# DSO_Power.net
KiCad netlist of a schematic drawn in Altium Designer
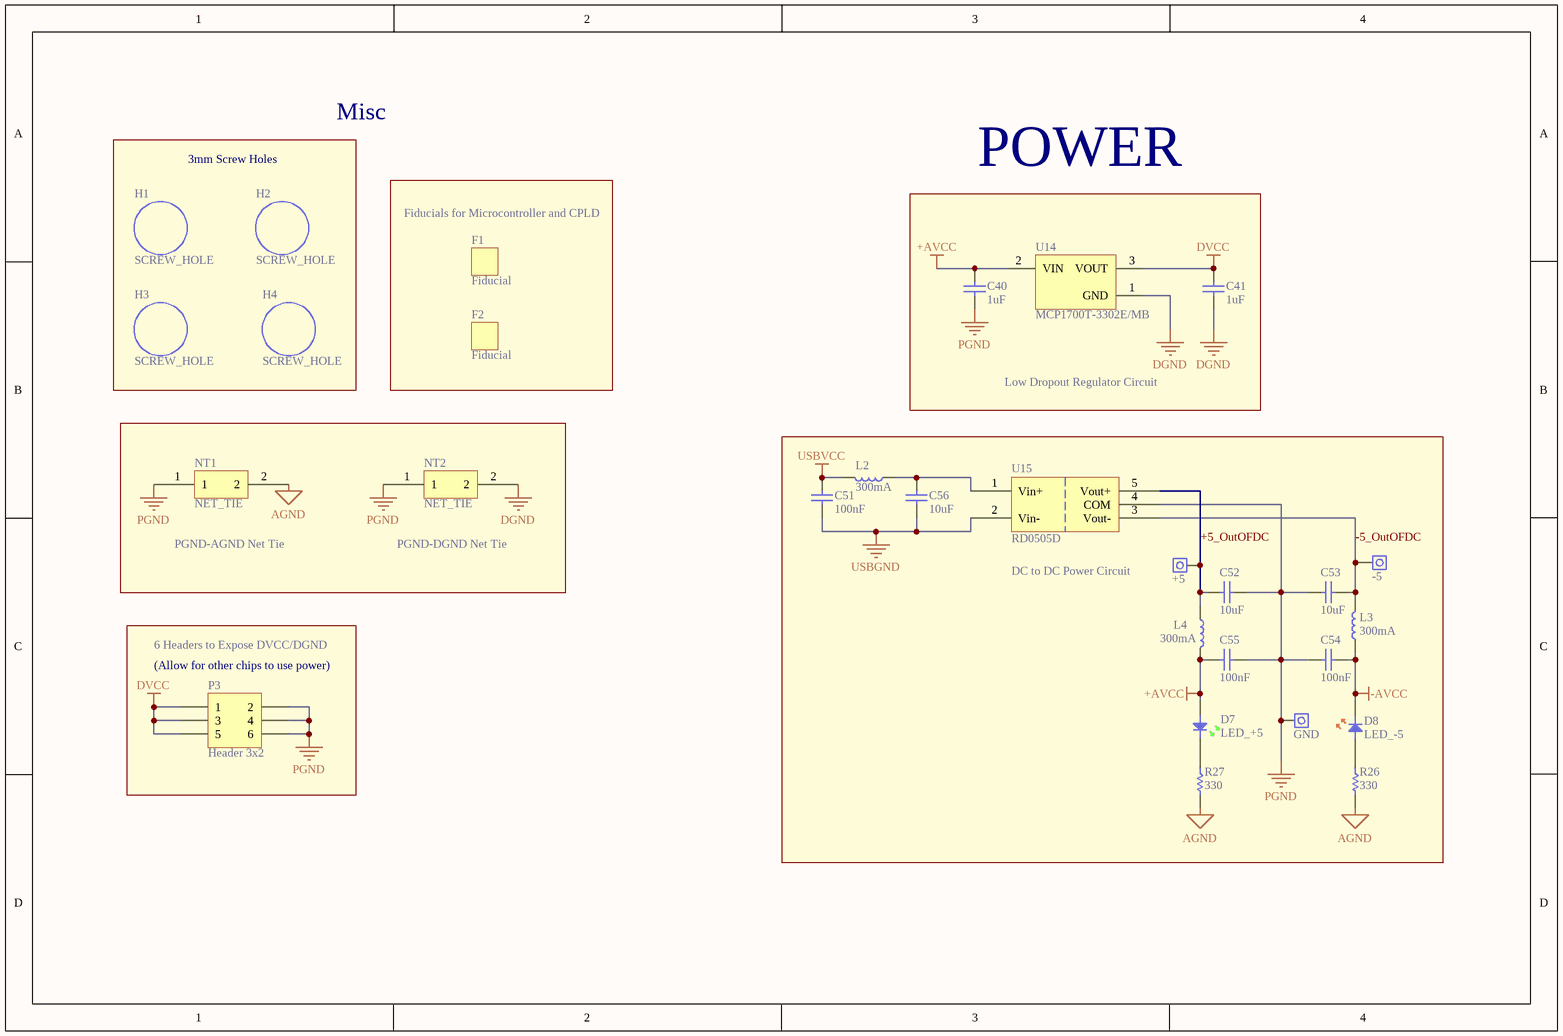
[diagram p0: DSO_Power.SchDoc]

(export (version "E")
  (design (tool "Eeschema 10.0.6"))
  (components
    (comp (ref "C40")
      (value "1uF")
      (footprint "0805C")
      (description "Capacitor")
      (fields (field (name "REVIEWED BY") "RM - 2018/08/05"))
      (libsource (lib "DSO") (part "C"))
    )
    (comp (ref "C41")
      (value "1uF")
      (footprint "0805C")
      (description "Capacitor")
      (fields (field (name "REVIEWED BY") "RM - 2018/08/05"))
      (libsource (lib "DSO") (part "C"))
    )
    (comp (ref "C51")
      (value "100nF")
      (footprint "0805C")
      (description "Capacitor")
      (fields (field (name "REVIEWED BY") "RM - 2018/08/05"))
      (libsource (lib "DSO") (part "C"))
    )
    (comp (ref "C52")
      (value "10uF")
      (footprint "0805C")
      (description "Capacitor")
      (fields (field (name "REVIEWED BY") "RM - 2018/08/05"))
      (libsource (lib "DSO") (part "C"))
    )
    (comp (ref "C53")
      (value "10uF")
      (footprint "0805C")
      (description "Capacitor")
      (fields (field (name "REVIEWED BY") "RM - 2018/08/05"))
      (libsource (lib "DSO") (part "C"))
    )
    (comp (ref "C54")
      (value "100nF")
      (footprint "0805C")
      (description "Capacitor")
      (fields (field (name "REVIEWED BY") "RM - 2018/08/05"))
      (libsource (lib "DSO") (part "C"))
    )
    (comp (ref "C55")
      (value "100nF")
      (footprint "0805C")
      (description "Capacitor")
      (fields (field (name "REVIEWED BY") "RM - 2018/08/05"))
      (libsource (lib "DSO") (part "C"))
    )
    (comp (ref "C56")
      (value "10uF")
      (footprint "0805C")
      (description "Capacitor")
      (fields (field (name "REVIEWED BY") "RM - 2018/08/05"))
      (libsource (lib "DSO") (part "C"))
    )
    (comp (ref "D7")
      (value "LED_+5")
      (footprint "0805D-GREEN")
      (description "Light Emitting Diode")
      (fields (field (name "REVIEWED BY") "RM - 2018/08/05"))
      (libsource (lib "DSO") (part "LED GREEN"))
    )
    (comp (ref "D8")
      (value "LED_-5")
      (footprint "0805D-RED")
      (description "Light Emitting Diode")
      (fields (field (name "REVIEWED BY") "RM - 2018/08/05"))
      (libsource (lib "DSO") (part "LED RED"))
    )
    (comp (ref "F1") (value "Fiducial") (footprint "Fiducial") (libsource (lib "DSO") (part "Fiducial")))
    (comp (ref "F2") (value "Fiducial") (footprint "Fiducial") (libsource (lib "DSO") (part "Fiducial")))
    (comp (ref "H1")
      (value "SCREW_HOLE")
      (footprint "SCREW_HOLE")
      (libsource (lib "DSO") (part "SCREW_HOLE"))
    )
    (comp (ref "H2")
      (value "SCREW_HOLE")
      (footprint "SCREW_HOLE")
      (libsource (lib "DSO") (part "SCREW_HOLE"))
    )
    (comp (ref "H3")
      (value "SCREW_HOLE")
      (footprint "SCREW_HOLE")
      (libsource (lib "DSO") (part "SCREW_HOLE"))
    )
    (comp (ref "H4")
      (value "SCREW_HOLE")
      (footprint "SCREW_HOLE")
      (libsource (lib "DSO") (part "SCREW_HOLE"))
    )
    (comp (ref "L2")
      (value "300mA")
      (footprint "0805")
      (description "Inductor")
      (fields (field (name "REVIEWED BY") "RM - 2018/08/05"))
      (libsource (lib "DSO") (part "I"))
    )
    (comp (ref "L3")
      (value "300mA")
      (footprint "0805")
      (description "Inductor")
      (fields (field (name "REVIEWED BY") "RM - 2018/08/05"))
      (libsource (lib "DSO") (part "I"))
    )
    (comp (ref "L4")
      (value "300mA")
      (footprint "0805")
      (description "Inductor")
      (fields (field (name "REVIEWED BY") "RM - 2018/08/05"))
      (libsource (lib "DSO") (part "I"))
    )
    (comp (ref "NT1")
      (value "NET_TIE")
      (footprint "NET_TIE")
      (description "Net Tie")
      (libsource (lib "DSO") (part "NET_TIE"))
    )
    (comp (ref "NT2")
      (value "NET_TIE")
      (footprint "NET_TIE")
      (description "Net Tie")
      (libsource (lib "DSO") (part "NET_TIE"))
    )
    (comp (ref "P3")
      (value "Header 3x2")
      (footprint "HDR3x2")
      (description "Header, 5-Pin")
      (fields (field (name "REVIEWED BY") "RM - 2018/08/05"))
      (libsource (lib "DSO") (part "Header 3x2"))
    )
    (comp (ref "R26")
      (value "330")
      (footprint "0805")
      (description "Resistor")
      (fields (field (name "REVIEWED BY") "RM - 2018/08/05"))
      (libsource (lib "DSO") (part "R"))
    )
    (comp (ref "R27")
      (value "330")
      (footprint "0805")
      (description "Resistor")
      (fields (field (name "REVIEWED BY") "RM - 2018/08/05"))
      (libsource (lib "DSO") (part "R"))
    )
    (comp (ref "TP9")
      (value "-5")
      (footprint "PIN 1.8mm")
      (description "Pad")
      (libsource (lib "DSO") (part "WIRE"))
    )
    (comp (ref "TP10")
      (value "GND")
      (footprint "PIN 1.8mm")
      (description "Pad")
      (libsource (lib "DSO") (part "WIRE"))
    )
    (comp (ref "TP11")
      (value "+5")
      (footprint "PIN 1.8mm")
      (description "Pad")
      (libsource (lib "DSO") (part "WIRE"))
    )
    (comp (ref "U14")
      (value "MCP1700T-3302E/MB")
      (footprint "SOT89")
      (description "Low Quiescent Current LDO, 3-Pin SOT-89, Extended Temperature, Tape and Reel")
      (fields (field (name "REVIEWED BY") "RM - 2018/08/05"))
      (libsource (lib "DSO") (part "MCP1700T"))
    )
    (comp (ref "U15")
      (value "RD0505D")
      (footprint "SIP_NMG")
      (description "(ADV) DC to DC converter 5V in +-5V out")
      (fields (field (name "REVIEWED BY") "RM - 2018/08/05"))
      (libsource (lib "DSO") (part "RD0505D"))
    )
  )
  (nets
    (net (code "1") (name "+AVCC") (class "Default")
      (node (ref "C40") (pin "1") (pinfunction "1_1") (pintype "passive"))
      (node (ref "C55") (pin "1") (pinfunction "1_1") (pintype "passive"))
      (node (ref "D7") (pin "A") (pinfunction "A_A") (pintype "passive"))
      (node (ref "L4") (pin "2") (pinfunction "2_2") (pintype "passive"))
      (node (ref "U14") (pin "2") (pinfunction "VIN_2") (pintype "power_in"))
    )
    (net (code "2") (name "-AVCC") (class "Default")
      (node (ref "C54") (pin "1") (pinfunction "1_1") (pintype "passive"))
      (node (ref "D8") (pin "K") (pinfunction "K_K") (pintype "passive"))
      (node (ref "L3") (pin "1") (pinfunction "1_1") (pintype "passive"))
    )
    (net (code "3") (name "/+5_OutOFDC") (class "Default")
      (node (ref "C52") (pin "1") (pinfunction "1_1") (pintype "passive"))
      (node (ref "L4") (pin "1") (pinfunction "1_1") (pintype "passive"))
      (node (ref "TP11") (pin "1") (pintype "passive"))
      (node (ref "U15") (pin "5") (pinfunction "Vout+_5") (pintype "passive"))
    )
    (net (code "4") (name "/-5_OutOFDC") (class "Default")
      (node (ref "C53") (pin "1") (pinfunction "1_1") (pintype "passive"))
      (node (ref "L3") (pin "2") (pinfunction "2_2") (pintype "passive"))
      (node (ref "TP9") (pin "1") (pintype "passive"))
      (node (ref "U15") (pin "3") (pinfunction "Vout-_3") (pintype "passive"))
    )
    (net (code "5") (name "AGND") (class "Default")
      (node (ref "NT1") (pin "2") (pinfunction "2_2") (pintype "passive"))
      (node (ref "R26") (pin "2") (pintype "passive"))
      (node (ref "R27") (pin "2") (pintype "passive"))
    )
    (net (code "6") (name "DGND") (class "Default")
      (node (ref "C41") (pin "2") (pinfunction "2_2") (pintype "passive"))
      (node (ref "NT2") (pin "2") (pinfunction "2_2") (pintype "passive"))
      (node (ref "U14") (pin "1") (pinfunction "GND_1") (pintype "power_in"))
    )
    (net (code "7") (name "DVCC") (class "Default")
      (node (ref "C41") (pin "1") (pinfunction "1_1") (pintype "passive"))
      (node (ref "P3") (pin "1") (pinfunction "1_1") (pintype "passive"))
      (node (ref "P3") (pin "3") (pinfunction "3_3") (pintype "passive"))
      (node (ref "P3") (pin "5") (pinfunction "5_5") (pintype "passive"))
      (node (ref "U14") (pin "3") (pinfunction "VOUT_3") (pintype "power_in"))
    )
    (net (code "8") (name "Net-(D7-PadK)") (class "Default")
      (node (ref "D7") (pin "K") (pinfunction "K_K") (pintype "passive"))
      (node (ref "R27") (pin "1") (pintype "passive"))
    )
    (net (code "9") (name "Net-(D8-PadA)") (class "Default")
      (node (ref "D8") (pin "A") (pinfunction "A_A") (pintype "passive"))
      (node (ref "R26") (pin "1") (pintype "passive"))
    )
    (net (code "10") (name "Net-(U15-Vin+)") (class "Default")
      (node (ref "C56") (pin "1") (pinfunction "1_1") (pintype "passive"))
      (node (ref "L2") (pin "1") (pinfunction "1_1") (pintype "passive"))
      (node (ref "U15") (pin "1") (pinfunction "Vin+_1") (pintype "passive"))
    )
    (net (code "11") (name "PGND") (class "Default")
      (node (ref "C40") (pin "2") (pinfunction "2_2") (pintype "passive"))
      (node (ref "C52") (pin "2") (pinfunction "2_2") (pintype "passive"))
      (node (ref "C53") (pin "2") (pinfunction "2_2") (pintype "passive"))
      (node (ref "C54") (pin "2") (pinfunction "2_2") (pintype "passive"))
      (node (ref "C55") (pin "2") (pinfunction "2_2") (pintype "passive"))
      (node (ref "NT1") (pin "1") (pinfunction "1_1") (pintype "passive"))
      (node (ref "NT2") (pin "1") (pinfunction "1_1") (pintype "passive"))
      (node (ref "P3") (pin "2") (pinfunction "2_2") (pintype "passive"))
      (node (ref "P3") (pin "4") (pinfunction "4_4") (pintype "passive"))
      (node (ref "P3") (pin "6") (pinfunction "6_6") (pintype "passive"))
      (node (ref "TP10") (pin "1") (pintype "passive"))
      (node (ref "U15") (pin "4") (pinfunction "COM_4") (pintype "passive"))
    )
    (net (code "12") (name "USBGND") (class "Default")
      (node (ref "C51") (pin "2") (pinfunction "2_2") (pintype "passive"))
      (node (ref "C56") (pin "2") (pinfunction "2_2") (pintype "passive"))
      (node (ref "U15") (pin "2") (pinfunction "Vin-_2") (pintype "passive"))
    )
    (net (code "13") (name "USBVCC") (class "Default")
      (node (ref "C51") (pin "1") (pinfunction "1_1") (pintype "passive"))
      (node (ref "L2") (pin "2") (pinfunction "2_2") (pintype "passive"))
    )
  )
)
